# temperaturesensor.net
KiCad netlist of a schematic drawn in Altium Designer
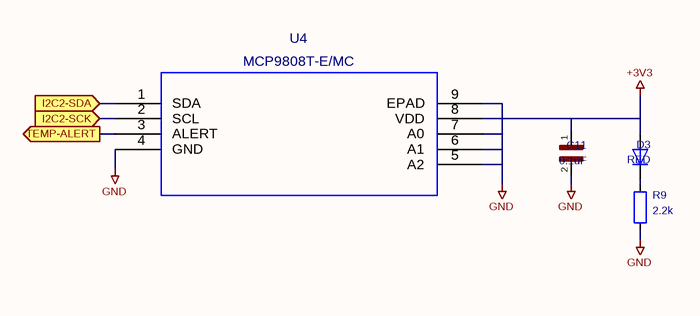
[diagram p0: temperaturesensor.SchDoc]

(export (version "E")
  (design (tool "Eeschema 10.0.6"))
  (components
    (comp (ref "C11") (value "0.1uF") (libsource (lib "Daughterboard_Symbols") (part "CL10B104KB8NNNL")))
    (comp (ref "D3") (value "RED") (libsource (lib "Simulation_SPICE") (part "DIODE")))
    (comp (ref "R9") (value "2.2k") (libsource (lib "Device") (part "R")))
    (comp (ref "U4") (value "MCP9808T-E/MC") (libsource (lib "MCP9808T-EMC") (part "MCP9808T-E/MC")))
  )
  (nets
    (net (code "1") (name "+3V3") (class "Default")
      (node (ref "C11") (pin "1") (pinfunction "1_1") (pintype "passive"))
      (node (ref "D3") (pin "1") (pinfunction "A_1") (pintype "passive"))
      (node (ref "U4") (pin "8") (pinfunction "VDD_8") (pintype "passive"))
    )
    (net (code "2") (name "/I2C2-SCK") (class "Default")
      (node (ref "U4") (pin "2") (pinfunction "SCL_2") (pintype "passive"))
    )
    (net (code "3") (name "/I2C2-SDA") (class "Default")
      (node (ref "U4") (pin "1") (pinfunction "SDA_1") (pintype "passive"))
    )
    (net (code "4") (name "/TEMP-ALERT") (class "Default")
      (node (ref "U4") (pin "3") (pinfunction "ALERT_3") (pintype "passive"))
    )
    (net (code "5") (name "GND") (class "Default")
      (node (ref "C11") (pin "2") (pinfunction "2_2") (pintype "passive"))
      (node (ref "R9") (pin "2") (pinfunction "2_2") (pintype "passive"))
      (node (ref "U4") (pin "4") (pinfunction "GND_4") (pintype "passive"))
      (node (ref "U4") (pin "5") (pinfunction "A2_5") (pintype "passive"))
      (node (ref "U4") (pin "6") (pinfunction "A1_6") (pintype "passive"))
      (node (ref "U4") (pin "7") (pinfunction "A0_7") (pintype "passive"))
      (node (ref "U4") (pin "9") (pinfunction "EPAD_9") (pintype "passive"))
    )
    (net (code "6") (name "Net-(D3-K)") (class "Default")
      (node (ref "D3") (pin "2") (pinfunction "K_2") (pintype "passive"))
      (node (ref "R9") (pin "1") (pinfunction "1_1") (pintype "passive"))
    )
  )
)
